# STM32RCv2.net
KiCad netlist of a schematic drawn in EasyEDA
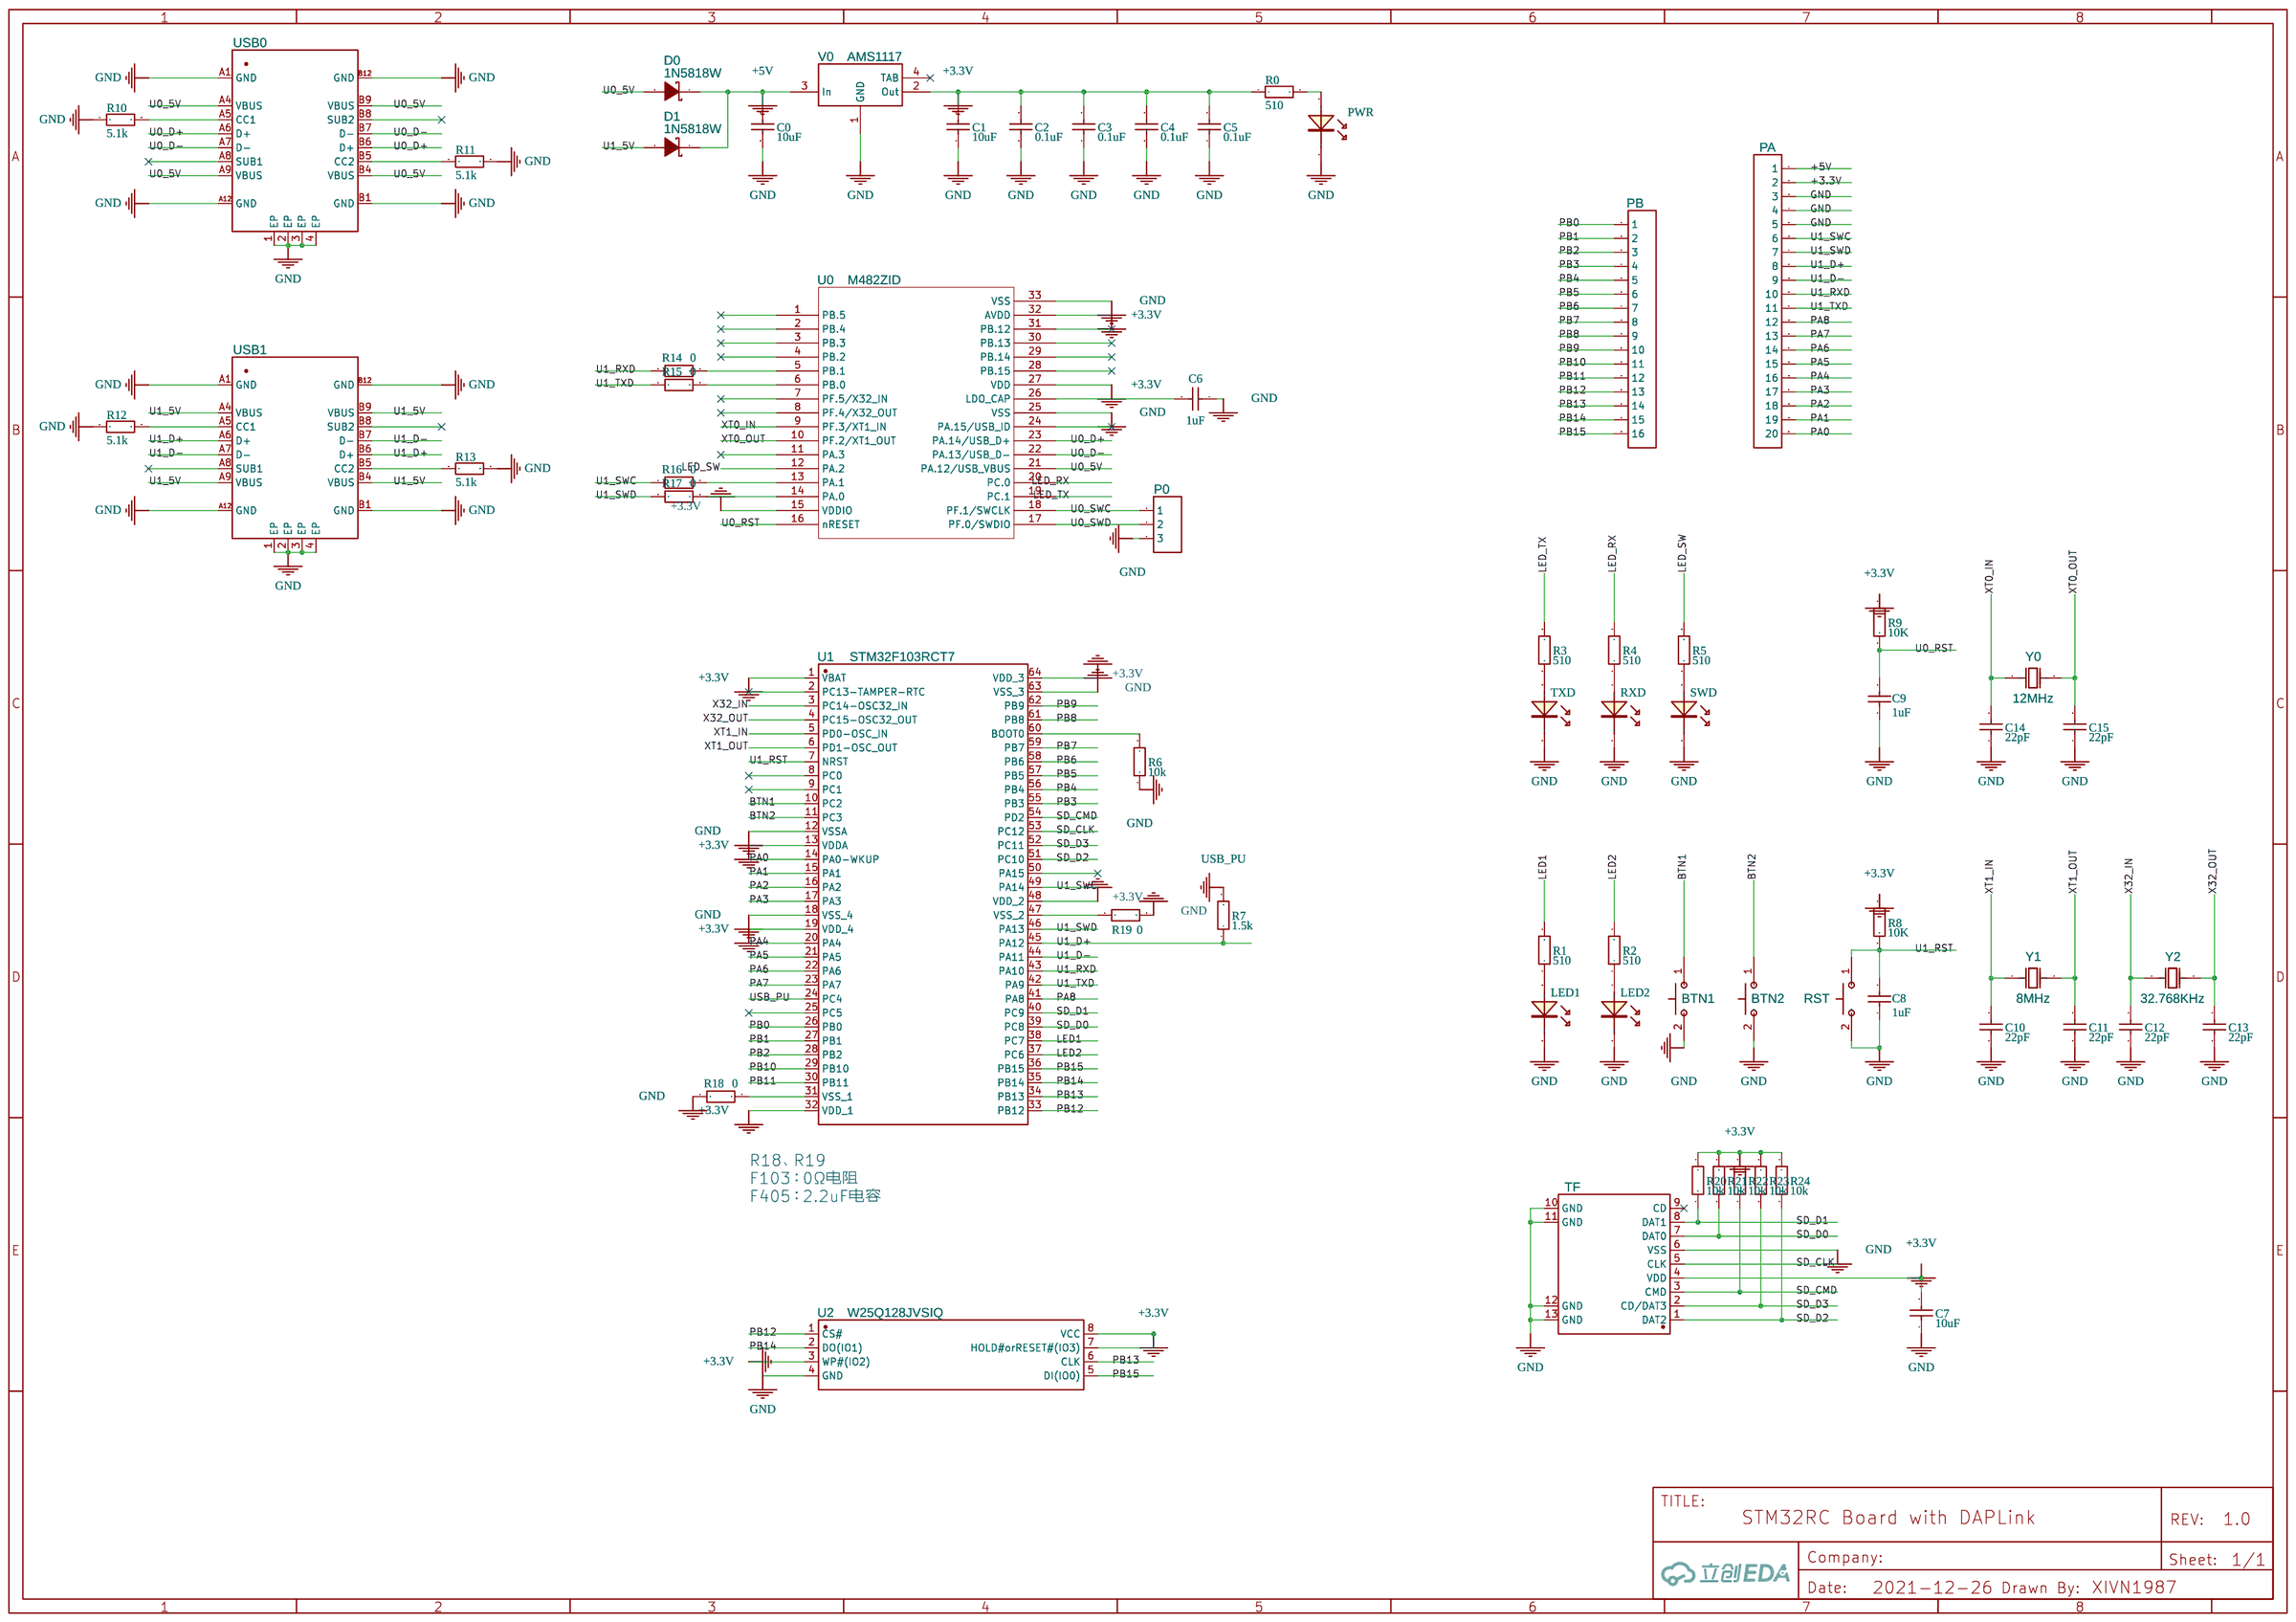
[diagram p0: schematic sheet]

(export (version "E")
  (design (tool "Eeschema 10.0.6"))
  (components
    (comp (ref "BTN1")
      (value "1TS002B-2600-4301")
      (fields (field (name "BOM_Supplier Part") "C318835"))
      (libsource (lib "") (part "1TS002B-2600-4301"))
    )
    (comp (ref "BTN2")
      (value "1TS002B-2600-4301")
      (fields (field (name "BOM_Supplier Part") "C318835"))
      (libsource (lib "") (part "1TS002B-2600-4301"))
    )
    (comp (ref "C0") (value "10uF") (libsource (lib "") (part "Unknown_530_-717")))
    (comp (ref "C1") (value "10uF") (libsource (lib "") (part "Unknown_670_-717")))
    (comp (ref "C2") (value "0.1uF") (libsource (lib "") (part "Unknown_715_-717")))
    (comp (ref "C3") (value "0.1uF") (libsource (lib "") (part "Unknown_760_-717")))
    (comp (ref "C4") (value "0.1uF") (libsource (lib "") (part "Unknown_805_-717")))
    (comp (ref "C5") (value "0.1uF") (libsource (lib "") (part "Unknown_850_-717")))
    (comp (ref "C6") (value "1uF") (libsource (lib "") (part "Unknown_855_-517")))
    (comp (ref "C7") (value "10uF") (libsource (lib "") (part "Unknown_1360_133")))
    (comp (ref "C8") (value "1uF") (libsource (lib "") (part "Unknown_1330_-92")))
    (comp (ref "C9") (value "1uF") (libsource (lib "") (part "Unknown_1330_-307")))
    (comp (ref "C10") (value "22pF") (libsource (lib "") (part "Unknown_1410_-72")))
    (comp (ref "C11") (value "22pF") (libsource (lib "") (part "Unknown_1470_-72")))
    (comp (ref "C12") (value "22pF") (libsource (lib "") (part "Unknown_1510_-72")))
    (comp (ref "C13") (value "22pF") (libsource (lib "") (part "Unknown_1570_-72")))
    (comp (ref "C14") (value "22pF") (libsource (lib "") (part "Unknown_1410_-287")))
    (comp (ref "C15") (value "22pF") (libsource (lib "") (part "Unknown_1470_-287")))
    (comp (ref "D0")
      (value "1N5818W")
      (fields (field (name "BOM_Supplier Part") "C437955"))
      (libsource (lib "") (part "1N5818W"))
    )
    (comp (ref "D1")
      (value "1N5818W")
      (fields (field (name "BOM_Supplier Part") "C437955"))
      (libsource (lib "") (part "1N5818W"))
    )
    (comp (ref "LED1") (value "NO") (libsource (lib "") (part "Unknown_1100_-112")))
    (comp (ref "LED2") (value "NO") (libsource (lib "") (part "Unknown_1150_-112")))
    (comp (ref "P0")
      (value "HDR-M-2.54_1x3")
      (fields (field (name "BOM_Supplier Part") "C180248"))
      (libsource (lib "") (part "HDR-M-2.54_1x3"))
    )
    (comp (ref "PA")
      (value "HDR-M-2.54_1x20")
      (fields (field (name "BOM_Supplier Part") "C50981"))
      (libsource (lib "") (part "HDR-M-2.54_1x20"))
    )
    (comp (ref "PB")
      (value "HDR-M-2.54_1x16")
      (fields (field (name "BOM_Supplier Part") "C50981"))
      (libsource (lib "") (part "HDR-M-2.54_1x16"))
    )
    (comp (ref "PWR") (value "NO") (libsource (lib "") (part "Unknown_940_-747")))
    (comp (ref "R0") (value "510") (libsource (lib "") (part "Unknown_920_-747")))
    (comp (ref "R1") (value "510") (libsource (lib "") (part "Unknown_1100_-142")))
    (comp (ref "R2") (value "510") (libsource (lib "") (part "Unknown_1150_-142")))
    (comp (ref "R3") (value "510") (libsource (lib "") (part "Unknown_1100_-357")))
    (comp (ref "R4") (value "510") (libsource (lib "") (part "Unknown_1150_-357")))
    (comp (ref "R5") (value "510") (libsource (lib "") (part "Unknown_1200_-357")))
    (comp (ref "R6") (value "10k") (libsource (lib "") (part "Unknown_810_-277")))
    (comp (ref "R7") (value "1.5k") (libsource (lib "") (part "Unknown_870_-167")))
    (comp (ref "R8") (value "10K") (libsource (lib "") (part "Unknown_1340_-142")))
    (comp (ref "R9") (value "10K") (libsource (lib "") (part "Unknown_1340_-357")))
    (comp (ref "R10") (value "5.1k") (libsource (lib "") (part "Unknown_90_-727")))
    (comp (ref "R11") (value "5.1k") (libsource (lib "") (part "Unknown_340_-697")))
    (comp (ref "R12") (value "5.1k") (libsource (lib "") (part "Unknown_90_-507")))
    (comp (ref "R13") (value "5.1k") (libsource (lib "") (part "Unknown_340_-477")))
    (comp (ref "R14") (value "0") (libsource (lib "") (part "Unknown_490_-547")))
    (comp (ref "R15") (value "0") (libsource (lib "") (part "Unknown_490_-537")))
    (comp (ref "R16") (value "0") (libsource (lib "") (part "Unknown_490_-467")))
    (comp (ref "R17") (value "0") (libsource (lib "") (part "Unknown_490_-457")))
    (comp (ref "R18") (value "0") (libsource (lib "") (part "Unknown_520_-27")))
    (comp (ref "R19") (value "0") (libsource (lib "") (part "Unknown_810_-157")))
    (comp (ref "R20") (value "10k") (libsource (lib "") (part "Unknown_1210_43")))
    (comp (ref "R21") (value "10k") (libsource (lib "") (part "Unknown_1225_43")))
    (comp (ref "R22") (value "10k") (libsource (lib "") (part "Unknown_1240_43")))
    (comp (ref "R23") (value "10k") (libsource (lib "") (part "Unknown_1255_43")))
    (comp (ref "R24") (value "10k") (libsource (lib "") (part "Unknown_1270_43")))
    (comp (ref "RST")
      (value "1TS002B-2600-4301")
      (fields (field (name "BOM_Supplier Part") "C318835"))
      (libsource (lib "") (part "1TS002B-2600-4301_1"))
    )
    (comp (ref "RXD") (value "NO") (libsource (lib "") (part "Unknown_1150_-327")))
    (comp (ref "SWD") (value "NO") (libsource (lib "") (part "Unknown_1200_-327")))
    (comp (ref "TF")
      (value "TF-01A_C2889258")
      (fields (field (name "BOM_Manufacturer Part") "TF-01A") (field (name "BOM_Supplier Part") "C2889258"))
      (libsource (lib "") (part "TF-01A_C2889258"))
    )
    (comp (ref "TXD") (value "NO") (libsource (lib "") (part "Unknown_1100_-327")))
    (comp (ref "U0") (value "M482ZID") (libsource (lib "") (part "M482ZID")))
    (comp (ref "U1")
      (value "STM32F103RCT7")
      (fields (field (name "BOM_Supplier Part") "C882165"))
      (libsource (lib "") (part "STM32F103RCT7"))
    )
    (comp (ref "U2")
      (value "W25Q128JVSIQ")
      (fields (field (name "BOM_Supplier Part") "C113767"))
      (libsource (lib "") (part "W25Q128JVSIQ"))
    )
    (comp (ref "USB0")
      (value "KH-TYPE-C-16P-T")
      (fields (field (name "BOM_Supplier Part") "C709358"))
      (libsource (lib "") (part "KH-TYPE-C-16P-T"))
    )
    (comp (ref "USB1")
      (value "KH-TYPE-C-16P-T")
      (fields (field (name "BOM_Supplier Part") "C709358"))
      (libsource (lib "") (part "KH-TYPE-C-16P-T"))
    )
    (comp (ref "V0")
      (value "AMS1117")
      (fields
        (field (name "BOM_Manufacturer Part") "AMS1117-2.5")
        (field (name "BOM_Supplier Part") "C12087")
      )
      (libsource (lib "") (part "AMS1117-2.5"))
    )
    (comp (ref "Y0")
      (value "12MHz")
      (fields
        (field (name "BOM_Manufacturer Part") "X503212MSB2GI")
        (field (name "BOM_Supplier Part") "C112573")
      )
      (libsource (lib "") (part "X503212MSB2GI"))
    )
    (comp (ref "Y1")
      (value "8MHz")
      (fields
        (field (name "BOM_Manufacturer Part") "X503212MSB2GI")
        (field (name "BOM_Supplier Part") "C112573")
      )
      (libsource (lib "") (part "X503212MSB2GI"))
    )
    (comp (ref "Y2")
      (value "32.768KHz")
      (fields
        (field (name "BOM_Manufacturer Part") "7LC32768F12UC")
        (field (name "BOM_Supplier Part") "C252398")
      )
      (libsource (lib "") (part "7LC32768F12UC"))
    )
  )
  (nets
    (net (code "1") (name "+3.3V") (class "Default")
      (node (ref "C1") (pin "2") (pinfunction "2_2") (pintype "unspecified"))
      (node (ref "C2") (pin "2") (pinfunction "2_2") (pintype "unspecified"))
      (node (ref "C3") (pin "2") (pinfunction "2_2") (pintype "unspecified"))
      (node (ref "C4") (pin "2") (pinfunction "2_2") (pintype "unspecified"))
      (node (ref "C5") (pin "2") (pinfunction "2_2") (pintype "unspecified"))
      (node (ref "C7") (pin "2") (pinfunction "2_2") (pintype "unspecified"))
      (node (ref "PA") (pin "2") (pinfunction "2_2") (pintype "unspecified"))
      (node (ref "R0") (pin "1") (pinfunction "1_1") (pintype "unspecified"))
      (node (ref "R20") (pin "1") (pinfunction "1_1") (pintype "unspecified"))
      (node (ref "R21") (pin "1") (pinfunction "1_1") (pintype "unspecified"))
      (node (ref "R22") (pin "1") (pinfunction "1_1") (pintype "unspecified"))
      (node (ref "R23") (pin "1") (pinfunction "1_1") (pintype "unspecified"))
      (node (ref "R24") (pin "1") (pinfunction "1_1") (pintype "unspecified"))
      (node (ref "R8") (pin "1") (pinfunction "1_1") (pintype "unspecified"))
      (node (ref "R9") (pin "1") (pinfunction "1_1") (pintype "unspecified"))
      (node (ref "TF") (pin "4") (pinfunction "VDD_4") (pintype "unspecified"))
      (node (ref "U0") (pin "15") (pinfunction "VDDIO_15") (pintype "unspecified"))
      (node (ref "U0") (pin "27") (pinfunction "VDD_27") (pintype "unspecified"))
      (node (ref "U0") (pin "32") (pinfunction "AVDD_32") (pintype "unspecified"))
      (node (ref "U1") (pin "1") (pinfunction "VBAT_1") (pintype "unspecified"))
      (node (ref "U1") (pin "13") (pinfunction "VDDA_13") (pintype "unspecified"))
      (node (ref "U1") (pin "19") (pinfunction "VDD_4_19") (pintype "unspecified"))
      (node (ref "U1") (pin "32") (pinfunction "VDD_1_32") (pintype "unspecified"))
      (node (ref "U1") (pin "48") (pinfunction "VDD_2_48") (pintype "unspecified"))
      (node (ref "U1") (pin "64") (pinfunction "VDD_3_64") (pintype "unspecified"))
      (node (ref "U2") (pin "3") (pinfunction "WP#(IO2)_3") (pintype "unspecified"))
      (node (ref "U2") (pin "7") (pinfunction "HOLD#orRESET#(IO3)_7") (pintype "unspecified"))
      (node (ref "U2") (pin "8") (pinfunction "VCC_8") (pintype "unspecified"))
      (node (ref "V0") (pin "2") (pinfunction "Out_2") (pintype "unspecified"))
    )
    (net (code "2") (name "+5V") (class "Default")
      (node (ref "C0") (pin "2") (pinfunction "2_2") (pintype "unspecified"))
      (node (ref "D0") (pin "1") (pinfunction "C_1") (pintype "unspecified"))
      (node (ref "D1") (pin "1") (pinfunction "C_1") (pintype "unspecified"))
      (node (ref "PA") (pin "1") (pinfunction "1_1") (pintype "unspecified"))
      (node (ref "V0") (pin "3") (pinfunction "In_3") (pintype "unspecified"))
    )
    (net (code "3") (name "/BTN1") (class "Default")
      (node (ref "BTN1") (pin "1") (pinfunction "A_1") (pintype "unspecified"))
      (node (ref "U1") (pin "10") (pinfunction "PC2_10") (pintype "unspecified"))
    )
    (net (code "4") (name "/BTN2") (class "Default")
      (node (ref "BTN2") (pin "1") (pinfunction "A_1") (pintype "unspecified"))
      (node (ref "U1") (pin "11") (pinfunction "PC3_11") (pintype "unspecified"))
    )
    (net (code "5") (name "/LED1") (class "Default")
      (node (ref "R1") (pin "2") (pinfunction "2_2") (pintype "unspecified"))
      (node (ref "U1") (pin "38") (pinfunction "PC7_38") (pintype "unspecified"))
    )
    (net (code "6") (name "/LED2") (class "Default")
      (node (ref "R2") (pin "2") (pinfunction "2_2") (pintype "unspecified"))
      (node (ref "U1") (pin "37") (pinfunction "PC6_37") (pintype "unspecified"))
    )
    (net (code "7") (name "/LED_RX") (class "Default")
      (node (ref "R4") (pin "2") (pinfunction "2_2") (pintype "unspecified"))
      (node (ref "U0") (pin "20") (pinfunction "PC.0_20") (pintype "unspecified"))
    )
    (net (code "8") (name "/LED_SW") (class "Default")
      (node (ref "R5") (pin "2") (pinfunction "2_2") (pintype "unspecified"))
      (node (ref "U0") (pin "12") (pinfunction "PA.2_12") (pintype "unspecified"))
    )
    (net (code "9") (name "/LED_TX") (class "Default")
      (node (ref "R3") (pin "2") (pinfunction "2_2") (pintype "unspecified"))
      (node (ref "U0") (pin "19") (pinfunction "PC.1_19") (pintype "unspecified"))
    )
    (net (code "10") (name "/PA0") (class "Default")
      (node (ref "PA") (pin "20") (pinfunction "20_20") (pintype "unspecified"))
      (node (ref "U1") (pin "14") (pinfunction "PA0-WKUP_14") (pintype "unspecified"))
    )
    (net (code "11") (name "/PA1") (class "Default")
      (node (ref "PA") (pin "19") (pinfunction "19_19") (pintype "unspecified"))
      (node (ref "U1") (pin "15") (pinfunction "PA1_15") (pintype "unspecified"))
    )
    (net (code "12") (name "/PA2") (class "Default")
      (node (ref "PA") (pin "18") (pinfunction "18_18") (pintype "unspecified"))
      (node (ref "U1") (pin "16") (pinfunction "PA2_16") (pintype "unspecified"))
    )
    (net (code "13") (name "/PA3") (class "Default")
      (node (ref "PA") (pin "17") (pinfunction "17_17") (pintype "unspecified"))
      (node (ref "U1") (pin "17") (pinfunction "PA3_17") (pintype "unspecified"))
    )
    (net (code "14") (name "/PA4") (class "Default")
      (node (ref "PA") (pin "16") (pinfunction "16_16") (pintype "unspecified"))
      (node (ref "U1") (pin "20") (pinfunction "PA4_20") (pintype "unspecified"))
    )
    (net (code "15") (name "/PA5") (class "Default")
      (node (ref "PA") (pin "15") (pinfunction "15_15") (pintype "unspecified"))
      (node (ref "U1") (pin "21") (pinfunction "PA5_21") (pintype "unspecified"))
    )
    (net (code "16") (name "/PA6") (class "Default")
      (node (ref "PA") (pin "14") (pinfunction "14_14") (pintype "unspecified"))
      (node (ref "U1") (pin "22") (pinfunction "PA6_22") (pintype "unspecified"))
    )
    (net (code "17") (name "/PA7") (class "Default")
      (node (ref "PA") (pin "13") (pinfunction "13_13") (pintype "unspecified"))
      (node (ref "U1") (pin "23") (pinfunction "PA7_23") (pintype "unspecified"))
    )
    (net (code "18") (name "/PA8") (class "Default")
      (node (ref "PA") (pin "12") (pinfunction "12_12") (pintype "unspecified"))
      (node (ref "U1") (pin "41") (pinfunction "PA8_41") (pintype "unspecified"))
    )
    (net (code "19") (name "/PB0") (class "Default")
      (node (ref "PB") (pin "1") (pinfunction "1_1") (pintype "unspecified"))
      (node (ref "U1") (pin "26") (pinfunction "PB0_26") (pintype "unspecified"))
    )
    (net (code "20") (name "/PB1") (class "Default")
      (node (ref "PB") (pin "2") (pinfunction "2_2") (pintype "unspecified"))
      (node (ref "U1") (pin "27") (pinfunction "PB1_27") (pintype "unspecified"))
    )
    (net (code "21") (name "/PB2") (class "Default")
      (node (ref "PB") (pin "3") (pinfunction "3_3") (pintype "unspecified"))
      (node (ref "U1") (pin "28") (pinfunction "PB2_28") (pintype "unspecified"))
    )
    (net (code "22") (name "/PB3") (class "Default")
      (node (ref "PB") (pin "4") (pinfunction "4_4") (pintype "unspecified"))
      (node (ref "U1") (pin "55") (pinfunction "PB3_55") (pintype "unspecified"))
    )
    (net (code "23") (name "/PB4") (class "Default")
      (node (ref "PB") (pin "5") (pinfunction "5_5") (pintype "unspecified"))
      (node (ref "U1") (pin "56") (pinfunction "PB4_56") (pintype "unspecified"))
    )
    (net (code "24") (name "/PB5") (class "Default")
      (node (ref "PB") (pin "6") (pinfunction "6_6") (pintype "unspecified"))
      (node (ref "U1") (pin "57") (pinfunction "PB5_57") (pintype "unspecified"))
    )
    (net (code "25") (name "/PB6") (class "Default")
      (node (ref "PB") (pin "7") (pinfunction "7_7") (pintype "unspecified"))
      (node (ref "U1") (pin "58") (pinfunction "PB6_58") (pintype "unspecified"))
    )
    (net (code "26") (name "/PB7") (class "Default")
      (node (ref "PB") (pin "8") (pinfunction "8_8") (pintype "unspecified"))
      (node (ref "U1") (pin "59") (pinfunction "PB7_59") (pintype "unspecified"))
    )
    (net (code "27") (name "/PB8") (class "Default")
      (node (ref "PB") (pin "9") (pinfunction "9_9") (pintype "unspecified"))
      (node (ref "U1") (pin "61") (pinfunction "PB8_61") (pintype "unspecified"))
    )
    (net (code "28") (name "/PB9") (class "Default")
      (node (ref "PB") (pin "10") (pinfunction "10_10") (pintype "unspecified"))
      (node (ref "U1") (pin "62") (pinfunction "PB9_62") (pintype "unspecified"))
    )
    (net (code "29") (name "/PB10") (class "Default")
      (node (ref "PB") (pin "11") (pinfunction "11_11") (pintype "unspecified"))
      (node (ref "U1") (pin "29") (pinfunction "PB10_29") (pintype "unspecified"))
    )
    (net (code "30") (name "/PB11") (class "Default")
      (node (ref "PB") (pin "12") (pinfunction "12_12") (pintype "unspecified"))
      (node (ref "U1") (pin "30") (pinfunction "PB11_30") (pintype "unspecified"))
    )
    (net (code "31") (name "/PB12") (class "Default")
      (node (ref "PB") (pin "13") (pinfunction "13_13") (pintype "unspecified"))
      (node (ref "U1") (pin "33") (pinfunction "PB12_33") (pintype "unspecified"))
      (node (ref "U2") (pin "1") (pinfunction "CS#_1") (pintype "unspecified"))
    )
    (net (code "32") (name "/PB13") (class "Default")
      (node (ref "PB") (pin "14") (pinfunction "14_14") (pintype "unspecified"))
      (node (ref "U1") (pin "34") (pinfunction "PB13_34") (pintype "unspecified"))
      (node (ref "U2") (pin "6") (pinfunction "CLK_6") (pintype "unspecified"))
    )
    (net (code "33") (name "/PB14") (class "Default")
      (node (ref "PB") (pin "15") (pinfunction "15_15") (pintype "unspecified"))
      (node (ref "U1") (pin "35") (pinfunction "PB14_35") (pintype "unspecified"))
      (node (ref "U2") (pin "2") (pinfunction "DO(IO1)_2") (pintype "unspecified"))
    )
    (net (code "34") (name "/PB15") (class "Default")
      (node (ref "PB") (pin "16") (pinfunction "16_16") (pintype "unspecified"))
      (node (ref "U1") (pin "36") (pinfunction "PB15_36") (pintype "unspecified"))
      (node (ref "U2") (pin "5") (pinfunction "DI(IO0)_5") (pintype "unspecified"))
    )
    (net (code "35") (name "/SD_CLK") (class "Default")
      (node (ref "TF") (pin "5") (pinfunction "CLK_5") (pintype "unspecified"))
      (node (ref "U1") (pin "53") (pinfunction "PC12_53") (pintype "unspecified"))
    )
    (net (code "36") (name "/SD_CMD") (class "Default")
      (node (ref "R22") (pin "2") (pinfunction "2_2") (pintype "unspecified"))
      (node (ref "TF") (pin "3") (pinfunction "CMD_3") (pintype "unspecified"))
      (node (ref "U1") (pin "54") (pinfunction "PD2_54") (pintype "unspecified"))
    )
    (net (code "37") (name "/SD_D0") (class "Default")
      (node (ref "R21") (pin "2") (pinfunction "2_2") (pintype "unspecified"))
      (node (ref "TF") (pin "7") (pinfunction "DAT0_7") (pintype "unspecified"))
      (node (ref "U1") (pin "39") (pinfunction "PC8_39") (pintype "unspecified"))
    )
    (net (code "38") (name "/SD_D1") (class "Default")
      (node (ref "R20") (pin "2") (pinfunction "2_2") (pintype "unspecified"))
      (node (ref "TF") (pin "8") (pinfunction "DAT1_8") (pintype "unspecified"))
      (node (ref "U1") (pin "40") (pinfunction "PC9_40") (pintype "unspecified"))
    )
    (net (code "39") (name "/SD_D2") (class "Default")
      (node (ref "R24") (pin "2") (pinfunction "2_2") (pintype "unspecified"))
      (node (ref "TF") (pin "1") (pinfunction "DAT2_1") (pintype "unspecified"))
      (node (ref "U1") (pin "51") (pinfunction "PC10_51") (pintype "unspecified"))
    )
    (net (code "40") (name "/SD_D3") (class "Default")
      (node (ref "R23") (pin "2") (pinfunction "2_2") (pintype "unspecified"))
      (node (ref "TF") (pin "2") (pinfunction "CD/DAT3_2") (pintype "unspecified"))
      (node (ref "U1") (pin "52") (pinfunction "PC11_52") (pintype "unspecified"))
    )
    (net (code "41") (name "/U0_5V") (class "Default")
      (node (ref "D0") (pin "2") (pinfunction "A_2") (pintype "unspecified"))
      (node (ref "U0") (pin "21") (pinfunction "PA.12/USB_VBUS_21") (pintype "unspecified"))
      (node (ref "USB0") (pin "A4") (pinfunction "VBUS_A4") (pintype "unspecified"))
      (node (ref "USB0") (pin "A9") (pinfunction "VBUS_A9") (pintype "unspecified"))
      (node (ref "USB0") (pin "B4") (pinfunction "VBUS_B4") (pintype "unspecified"))
      (node (ref "USB0") (pin "B9") (pinfunction "VBUS_B9") (pintype "unspecified"))
    )
    (net (code "42") (name "/U0_D+") (class "Default")
      (node (ref "U0") (pin "23") (pinfunction "PA.14/USB_D+_23") (pintype "unspecified"))
      (node (ref "USB0") (pin "A6") (pinfunction "D+_A6") (pintype "unspecified"))
      (node (ref "USB0") (pin "B6") (pinfunction "D+_B6") (pintype "unspecified"))
    )
    (net (code "43") (name "/U0_D-") (class "Default")
      (node (ref "U0") (pin "22") (pinfunction "PA.13/USB_D-_22") (pintype "unspecified"))
      (node (ref "USB0") (pin "A7") (pinfunction "D-_A7") (pintype "unspecified"))
      (node (ref "USB0") (pin "B7") (pinfunction "D-_B7") (pintype "unspecified"))
    )
    (net (code "44") (name "/U0_RST") (class "Default")
      (node (ref "C9") (pin "2") (pinfunction "2_2") (pintype "unspecified"))
      (node (ref "R9") (pin "2") (pinfunction "2_2") (pintype "unspecified"))
      (node (ref "U0") (pin "16") (pinfunction "nRESET_16") (pintype "unspecified"))
    )
    (net (code "45") (name "/U0_SWC") (class "Default")
      (node (ref "P0") (pin "1") (pinfunction "1_1") (pintype "input"))
      (node (ref "U0") (pin "18") (pinfunction "PF.1/SWCLK_18") (pintype "unspecified"))
    )
    (net (code "46") (name "/U0_SWD") (class "Default")
      (node (ref "P0") (pin "2") (pinfunction "2_2") (pintype "input"))
      (node (ref "U0") (pin "17") (pinfunction "PF.0/SWDIO_17") (pintype "unspecified"))
    )
    (net (code "47") (name "/U1_5V") (class "Default")
      (node (ref "D1") (pin "2") (pinfunction "A_2") (pintype "unspecified"))
      (node (ref "USB1") (pin "A4") (pinfunction "VBUS_A4") (pintype "unspecified"))
      (node (ref "USB1") (pin "A9") (pinfunction "VBUS_A9") (pintype "unspecified"))
      (node (ref "USB1") (pin "B4") (pinfunction "VBUS_B4") (pintype "unspecified"))
      (node (ref "USB1") (pin "B9") (pinfunction "VBUS_B9") (pintype "unspecified"))
    )
    (net (code "48") (name "/U1_D+") (class "Default")
      (node (ref "PA") (pin "8") (pinfunction "8_8") (pintype "unspecified"))
      (node (ref "R7") (pin "1") (pinfunction "1_1") (pintype "unspecified"))
      (node (ref "U1") (pin "45") (pinfunction "PA12_45") (pintype "unspecified"))
      (node (ref "USB1") (pin "A6") (pinfunction "D+_A6") (pintype "unspecified"))
      (node (ref "USB1") (pin "B6") (pinfunction "D+_B6") (pintype "unspecified"))
    )
    (net (code "49") (name "/U1_D-") (class "Default")
      (node (ref "PA") (pin "9") (pinfunction "9_9") (pintype "unspecified"))
      (node (ref "U1") (pin "44") (pinfunction "PA11_44") (pintype "unspecified"))
      (node (ref "USB1") (pin "A7") (pinfunction "D-_A7") (pintype "unspecified"))
      (node (ref "USB1") (pin "B7") (pinfunction "D-_B7") (pintype "unspecified"))
    )
    (net (code "50") (name "/U1_RST") (class "Default")
      (node (ref "C8") (pin "2") (pinfunction "2_2") (pintype "unspecified"))
      (node (ref "R8") (pin "2") (pinfunction "2_2") (pintype "unspecified"))
      (node (ref "RST") (pin "1") (pinfunction "A_1") (pintype "unspecified"))
      (node (ref "U1") (pin "7") (pinfunction "NRST_7") (pintype "unspecified"))
    )
    (net (code "51") (name "/U1_RXD") (class "Default")
      (node (ref "PA") (pin "10") (pinfunction "10_10") (pintype "unspecified"))
      (node (ref "R14") (pin "1") (pinfunction "1_1") (pintype "unspecified"))
      (node (ref "U1") (pin "43") (pinfunction "PA10_43") (pintype "unspecified"))
    )
    (net (code "52") (name "/U1_SWC") (class "Default")
      (node (ref "PA") (pin "6") (pinfunction "6_6") (pintype "unspecified"))
      (node (ref "R16") (pin "1") (pinfunction "1_1") (pintype "unspecified"))
      (node (ref "U1") (pin "49") (pinfunction "PA14_49") (pintype "unspecified"))
    )
    (net (code "53") (name "/U1_SWD") (class "Default")
      (node (ref "PA") (pin "7") (pinfunction "7_7") (pintype "unspecified"))
      (node (ref "R17") (pin "1") (pinfunction "1_1") (pintype "unspecified"))
      (node (ref "U1") (pin "46") (pinfunction "PA13_46") (pintype "unspecified"))
    )
    (net (code "54") (name "/U1_TXD") (class "Default")
      (node (ref "PA") (pin "11") (pinfunction "11_11") (pintype "unspecified"))
      (node (ref "R15") (pin "1") (pinfunction "1_1") (pintype "unspecified"))
      (node (ref "U1") (pin "42") (pinfunction "PA9_42") (pintype "unspecified"))
    )
    (net (code "55") (name "/X32_IN") (class "Default")
      (node (ref "C12") (pin "2") (pinfunction "2_2") (pintype "unspecified"))
      (node (ref "U1") (pin "3") (pinfunction "PC14-OSC32_IN_3") (pintype "unspecified"))
      (node (ref "Y2") (pin "1") (pinfunction "OSC1_1") (pintype "input"))
    )
    (net (code "56") (name "/X32_OUT") (class "Default")
      (node (ref "C13") (pin "2") (pinfunction "2_2") (pintype "unspecified"))
      (node (ref "U1") (pin "4") (pinfunction "PC15-OSC32_OUT_4") (pintype "unspecified"))
      (node (ref "Y2") (pin "2") (pinfunction "OSC2_2") (pintype "input"))
    )
    (net (code "57") (name "/XT0_IN") (class "Default")
      (node (ref "C14") (pin "2") (pinfunction "2_2") (pintype "unspecified"))
      (node (ref "U0") (pin "9") (pinfunction "PF.3/XT1_IN_9") (pintype "unspecified"))
      (node (ref "Y0") (pin "1") (pinfunction "OSC1_1") (pintype "input"))
    )
    (net (code "58") (name "/XT0_OUT") (class "Default")
      (node (ref "C15") (pin "2") (pinfunction "2_2") (pintype "unspecified"))
      (node (ref "U0") (pin "10") (pinfunction "PF.2/XT1_OUT_10") (pintype "unspecified"))
      (node (ref "Y0") (pin "2") (pinfunction "OSC2_2") (pintype "input"))
    )
    (net (code "59") (name "/XT1_IN") (class "Default")
      (node (ref "C10") (pin "2") (pinfunction "2_2") (pintype "unspecified"))
      (node (ref "U1") (pin "5") (pinfunction "PD0-OSC_IN_5") (pintype "unspecified"))
      (node (ref "Y1") (pin "1") (pinfunction "OSC1_1") (pintype "input"))
    )
    (net (code "60") (name "/XT1_OUT") (class "Default")
      (node (ref "C11") (pin "2") (pinfunction "2_2") (pintype "unspecified"))
      (node (ref "U1") (pin "6") (pinfunction "PD1-OSC_OUT_6") (pintype "unspecified"))
      (node (ref "Y1") (pin "2") (pinfunction "OSC2_2") (pintype "input"))
    )
    (net (code "61") (name "GND") (class "Default")
      (node (ref "BTN1") (pin "2") (pinfunction "B_2") (pintype "unspecified"))
      (node (ref "BTN2") (pin "2") (pinfunction "B_2") (pintype "unspecified"))
      (node (ref "C0") (pin "1") (pinfunction "1_1") (pintype "unspecified"))
      (node (ref "C1") (pin "1") (pinfunction "1_1") (pintype "unspecified"))
      (node (ref "C10") (pin "1") (pinfunction "1_1") (pintype "unspecified"))
      (node (ref "C11") (pin "1") (pinfunction "1_1") (pintype "unspecified"))
      (node (ref "C12") (pin "1") (pinfunction "1_1") (pintype "unspecified"))
      (node (ref "C13") (pin "1") (pinfunction "1_1") (pintype "unspecified"))
      (node (ref "C14") (pin "1") (pinfunction "1_1") (pintype "unspecified"))
      (node (ref "C15") (pin "1") (pinfunction "1_1") (pintype "unspecified"))
      (node (ref "C2") (pin "1") (pinfunction "1_1") (pintype "unspecified"))
      (node (ref "C3") (pin "1") (pinfunction "1_1") (pintype "unspecified"))
      (node (ref "C4") (pin "1") (pinfunction "1_1") (pintype "unspecified"))
      (node (ref "C5") (pin "1") (pinfunction "1_1") (pintype "unspecified"))
      (node (ref "C6") (pin "1") (pinfunction "1_1") (pintype "unspecified"))
      (node (ref "C7") (pin "1") (pinfunction "1_1") (pintype "unspecified"))
      (node (ref "C8") (pin "1") (pinfunction "1_1") (pintype "unspecified"))
      (node (ref "C9") (pin "1") (pinfunction "1_1") (pintype "unspecified"))
      (node (ref "LED1") (pin "2") (pinfunction "K_2") (pintype "unspecified"))
      (node (ref "LED2") (pin "2") (pinfunction "K_2") (pintype "unspecified"))
      (node (ref "P0") (pin "3") (pinfunction "3_3") (pintype "input"))
      (node (ref "PA") (pin "3") (pinfunction "3_3") (pintype "unspecified"))
      (node (ref "PA") (pin "4") (pinfunction "4_4") (pintype "unspecified"))
      (node (ref "PA") (pin "5") (pinfunction "5_5") (pintype "unspecified"))
      (node (ref "PWR") (pin "2") (pinfunction "K_2") (pintype "unspecified"))
      (node (ref "R10") (pin "1") (pinfunction "1_1") (pintype "unspecified"))
      (node (ref "R11") (pin "2") (pinfunction "2_2") (pintype "unspecified"))
      (node (ref "R12") (pin "1") (pinfunction "1_1") (pintype "unspecified"))
      (node (ref "R13") (pin "2") (pinfunction "2_2") (pintype "unspecified"))
      (node (ref "R18") (pin "1") (pinfunction "1_1") (pintype "unspecified"))
      (node (ref "R19") (pin "2") (pinfunction "2_2") (pintype "unspecified"))
      (node (ref "R6") (pin "1") (pinfunction "1_1") (pintype "unspecified"))
      (node (ref "RST") (pin "2") (pinfunction "B_2") (pintype "unspecified"))
      (node (ref "RXD") (pin "2") (pinfunction "K_2") (pintype "unspecified"))
      (node (ref "SWD") (pin "2") (pinfunction "K_2") (pintype "unspecified"))
      (node (ref "TF") (pin "10") (pinfunction "GND_10") (pintype "unspecified"))
      (node (ref "TF") (pin "11") (pinfunction "GND_11") (pintype "unspecified"))
      (node (ref "TF") (pin "12") (pinfunction "GND_12") (pintype "unspecified"))
      (node (ref "TF") (pin "13") (pinfunction "GND_13") (pintype "unspecified"))
      (node (ref "TF") (pin "6") (pinfunction "VSS_6") (pintype "unspecified"))
      (node (ref "TXD") (pin "2") (pinfunction "K_2") (pintype "unspecified"))
      (node (ref "U0") (pin "25") (pinfunction "VSS_25") (pintype "unspecified"))
      (node (ref "U0") (pin "33") (pinfunction "VSS_33") (pintype "unspecified"))
      (node (ref "U1") (pin "12") (pinfunction "VSSA_12") (pintype "unspecified"))
      (node (ref "U1") (pin "18") (pinfunction "VSS_4_18") (pintype "unspecified"))
      (node (ref "U1") (pin "63") (pinfunction "VSS_3_63") (pintype "unspecified"))
      (node (ref "U2") (pin "4") (pinfunction "GND_4") (pintype "unspecified"))
      (node (ref "USB0") (pin "1") (pinfunction "EP_1") (pintype "unspecified"))
      (node (ref "USB0") (pin "2") (pinfunction "EP_2") (pintype "unspecified"))
      (node (ref "USB0") (pin "3") (pinfunction "EP_3") (pintype "unspecified"))
      (node (ref "USB0") (pin "4") (pinfunction "EP_4") (pintype "unspecified"))
      (node (ref "USB0") (pin "A1") (pinfunction "GND_A1") (pintype "unspecified"))
      (node (ref "USB0") (pin "A12") (pinfunction "GND_A12") (pintype "unspecified"))
      (node (ref "USB0") (pin "B1") (pinfunction "GND_B1") (pintype "unspecified"))
      (node (ref "USB0") (pin "B12") (pinfunction "GND_B12") (pintype "unspecified"))
      (node (ref "USB1") (pin "1") (pinfunction "EP_1") (pintype "unspecified"))
      (node (ref "USB1") (pin "2") (pinfunction "EP_2") (pintype "unspecified"))
      (node (ref "USB1") (pin "3") (pinfunction "EP_3") (pintype "unspecified"))
      (node (ref "USB1") (pin "4") (pinfunction "EP_4") (pintype "unspecified"))
      (node (ref "USB1") (pin "A1") (pinfunction "GND_A1") (pintype "unspecified"))
      (node (ref "USB1") (pin "A12") (pinfunction "GND_A12") (pintype "unspecified"))
      (node (ref "USB1") (pin "B1") (pinfunction "GND_B1") (pintype "unspecified"))
      (node (ref "USB1") (pin "B12") (pinfunction "GND_B12") (pintype "unspecified"))
      (node (ref "V0") (pin "1") (pinfunction "GND_1") (pintype "unspecified"))
    )
    (net (code "62") (name "Net-(LED1-A)") (class "Default")
      (node (ref "LED1") (pin "1") (pinfunction "A_1") (pintype "unspecified"))
      (node (ref "R1") (pin "1") (pinfunction "1_1") (pintype "unspecified"))
    )
    (net (code "63") (name "Net-(LED2-A)") (class "Default")
      (node (ref "LED2") (pin "1") (pinfunction "A_1") (pintype "unspecified"))
      (node (ref "R2") (pin "1") (pinfunction "1_1") (pintype "unspecified"))
    )
    (net (code "64") (name "Net-(PWR-A)") (class "Default")
      (node (ref "PWR") (pin "1") (pinfunction "A_1") (pintype "unspecified"))
      (node (ref "R0") (pin "2") (pinfunction "2_2") (pintype "unspecified"))
    )
    (net (code "65") (name "Net-(RXD-A)") (class "Default")
      (node (ref "R4") (pin "1") (pinfunction "1_1") (pintype "unspecified"))
      (node (ref "RXD") (pin "1") (pinfunction "A_1") (pintype "unspecified"))
    )
    (net (code "66") (name "Net-(SWD-A)") (class "Default")
      (node (ref "R5") (pin "1") (pinfunction "1_1") (pintype "unspecified"))
      (node (ref "SWD") (pin "1") (pinfunction "A_1") (pintype "unspecified"))
    )
    (net (code "67") (name "Net-(TXD-A)") (class "Default")
      (node (ref "R3") (pin "1") (pinfunction "1_1") (pintype "unspecified"))
      (node (ref "TXD") (pin "1") (pinfunction "A_1") (pintype "unspecified"))
    )
    (net (code "68") (name "Net-(U0-LDO_CAP)") (class "Default")
      (node (ref "C6") (pin "2") (pinfunction "2_2") (pintype "unspecified"))
      (node (ref "U0") (pin "26") (pinfunction "LDO_CAP_26") (pintype "unspecified"))
    )
    (net (code "69") (name "Net-(U0-PA.0)") (class "Default")
      (node (ref "R17") (pin "2") (pinfunction "2_2") (pintype "unspecified"))
      (node (ref "U0") (pin "14") (pinfunction "PA.0_14") (pintype "unspecified"))
    )
    (net (code "70") (name "Net-(U0-PA.1)") (class "Default")
      (node (ref "R16") (pin "2") (pinfunction "2_2") (pintype "unspecified"))
      (node (ref "U0") (pin "13") (pinfunction "PA.1_13") (pintype "unspecified"))
    )
    (net (code "71") (name "Net-(U0-PB.0)") (class "Default")
      (node (ref "R15") (pin "2") (pinfunction "2_2") (pintype "unspecified"))
      (node (ref "U0") (pin "6") (pinfunction "PB.0_6") (pintype "unspecified"))
    )
    (net (code "72") (name "Net-(U0-PB.1)") (class "Default")
      (node (ref "R14") (pin "2") (pinfunction "2_2") (pintype "unspecified"))
      (node (ref "U0") (pin "5") (pinfunction "PB.1_5") (pintype "unspecified"))
    )
    (net (code "73") (name "Net-(U1-BOOT0)") (class "Default")
      (node (ref "R6") (pin "2") (pinfunction "2_2") (pintype "unspecified"))
      (node (ref "U1") (pin "60") (pinfunction "BOOT0_60") (pintype "unspecified"))
    )
    (net (code "74") (name "Net-(U1-VSS_1)") (class "Default")
      (node (ref "R18") (pin "2") (pinfunction "2_2") (pintype "unspecified"))
      (node (ref "U1") (pin "31") (pinfunction "VSS_1_31") (pintype "unspecified"))
    )
    (net (code "75") (name "Net-(U1-VSS_2)") (class "Default")
      (node (ref "R19") (pin "1") (pinfunction "1_1") (pintype "unspecified"))
      (node (ref "U1") (pin "47") (pinfunction "VSS_2_47") (pintype "unspecified"))
    )
    (net (code "76") (name "Net-(USB0-CC1)") (class "Default")
      (node (ref "R10") (pin "2") (pinfunction "2_2") (pintype "unspecified"))
      (node (ref "USB0") (pin "A5") (pinfunction "CC1_A5") (pintype "unspecified"))
    )
    (net (code "77") (name "Net-(USB0-CC2)") (class "Default")
      (node (ref "R11") (pin "1") (pinfunction "1_1") (pintype "unspecified"))
      (node (ref "USB0") (pin "B5") (pinfunction "CC2_B5") (pintype "unspecified"))
    )
    (net (code "78") (name "Net-(USB1-CC1)") (class "Default")
      (node (ref "R12") (pin "2") (pinfunction "2_2") (pintype "unspecified"))
      (node (ref "USB1") (pin "A5") (pinfunction "CC1_A5") (pintype "unspecified"))
    )
    (net (code "79") (name "Net-(USB1-CC2)") (class "Default")
      (node (ref "R13") (pin "1") (pinfunction "1_1") (pintype "unspecified"))
      (node (ref "USB1") (pin "B5") (pinfunction "CC2_B5") (pintype "unspecified"))
    )
    (net (code "80") (name "USB_PU") (class "Default")
      (node (ref "R7") (pin "2") (pinfunction "2_2") (pintype "unspecified"))
      (node (ref "U1") (pin "24") (pinfunction "PC4_24") (pintype "unspecified"))
    )
    (net (code "81") (name "unconnected-(TF-CD-Pad9)") (class "Default")
      (node (ref "TF") (pin "9") (pinfunction "CD_9") (pintype "unspecified+no_connect"))
    )
    (net (code "82") (name "unconnected-(U0-PA.3-Pad11)") (class "Default")
      (node (ref "U0") (pin "11") (pinfunction "PA.3_11") (pintype "unspecified+no_connect"))
    )
    (net (code "83") (name "unconnected-(U0-PA.15{slash}USB_ID-Pad24)") (class "Default")
      (node (ref "U0") (pin "24") (pinfunction "PA.15/USB_ID_24") (pintype "unspecified+no_connect"))
    )
    (net (code "84") (name "unconnected-(U0-PB.2-Pad4)") (class "Default")
      (node (ref "U0") (pin "4") (pinfunction "PB.2_4") (pintype "unspecified+no_connect"))
    )
    (net (code "85") (name "unconnected-(U0-PB.3-Pad3)") (class "Default")
      (node (ref "U0") (pin "3") (pinfunction "PB.3_3") (pintype "unspecified+no_connect"))
    )
    (net (code "86") (name "unconnected-(U0-PB.4-Pad2)") (class "Default")
      (node (ref "U0") (pin "2") (pinfunction "PB.4_2") (pintype "unspecified+no_connect"))
    )
    (net (code "87") (name "unconnected-(U0-PB.5-Pad1)") (class "Default")
      (node (ref "U0") (pin "1") (pinfunction "PB.5_1") (pintype "unspecified+no_connect"))
    )
    (net (code "88") (name "unconnected-(U0-PB.12-Pad31)") (class "Default")
      (node (ref "U0") (pin "31") (pinfunction "PB.12_31") (pintype "unspecified+no_connect"))
    )
    (net (code "89") (name "unconnected-(U0-PB.13-Pad30)") (class "Default")
      (node (ref "U0") (pin "30") (pinfunction "PB.13_30") (pintype "unspecified+no_connect"))
    )
    (net (code "90") (name "unconnected-(U0-PB.14-Pad29)") (class "Default")
      (node (ref "U0") (pin "29") (pinfunction "PB.14_29") (pintype "unspecified+no_connect"))
    )
    (net (code "91") (name "unconnected-(U0-PB.15-Pad28)") (class "Default")
      (node (ref "U0") (pin "28") (pinfunction "PB.15_28") (pintype "unspecified+no_connect"))
    )
    (net (code "92") (name "unconnected-(U0-PF.4{slash}X32_OUT-Pad8)") (class "Default")
      (node (ref "U0") (pin "8") (pinfunction "PF.4/X32_OUT_8") (pintype "unspecified+no_connect"))
    )
    (net (code "93") (name "unconnected-(U0-PF.5{slash}X32_IN-Pad7)") (class "Default")
      (node (ref "U0") (pin "7") (pinfunction "PF.5/X32_IN_7") (pintype "unspecified+no_connect"))
    )
    (net (code "94") (name "unconnected-(U1-PA15-Pad50)") (class "Default")
      (node (ref "U1") (pin "50") (pinfunction "PA15_50") (pintype "unspecified+no_connect"))
    )
    (net (code "95") (name "unconnected-(U1-PC0-Pad8)") (class "Default")
      (node (ref "U1") (pin "8") (pinfunction "PC0_8") (pintype "unspecified+no_connect"))
    )
    (net (code "96") (name "unconnected-(U1-PC1-Pad9)") (class "Default")
      (node (ref "U1") (pin "9") (pinfunction "PC1_9") (pintype "unspecified+no_connect"))
    )
    (net (code "97") (name "unconnected-(U1-PC5-Pad25)") (class "Default")
      (node (ref "U1") (pin "25") (pinfunction "PC5_25") (pintype "unspecified+no_connect"))
    )
    (net (code "98") (name "unconnected-(U1-PC13-TAMPER-RTC-Pad2)") (class "Default")
      (node (ref "U1") (pin "2") (pinfunction "PC13-TAMPER-RTC_2") (pintype "unspecified+no_connect"))
    )
    (net (code "99") (name "unconnected-(USB0-SUB1-PadA8)") (class "Default")
      (node (ref "USB0") (pin "A8") (pinfunction "SUB1_A8") (pintype "unspecified+no_connect"))
    )
    (net (code "100") (name "unconnected-(USB0-SUB2-PadB8)") (class "Default")
      (node (ref "USB0") (pin "B8") (pinfunction "SUB2_B8") (pintype "unspecified+no_connect"))
    )
    (net (code "101") (name "unconnected-(USB1-SUB1-PadA8)") (class "Default")
      (node (ref "USB1") (pin "A8") (pinfunction "SUB1_A8") (pintype "unspecified+no_connect"))
    )
    (net (code "102") (name "unconnected-(USB1-SUB2-PadB8)") (class "Default")
      (node (ref "USB1") (pin "B8") (pinfunction "SUB2_B8") (pintype "unspecified+no_connect"))
    )
    (net (code "103") (name "unconnected-(V0-TAB-Pad4)") (class "Default")
      (node (ref "V0") (pin "4") (pinfunction "TAB_4") (pintype "unspecified+no_connect"))
    )
  )
)
